# MOTOR_DRIVER.net
KiCad netlist of a schematic drawn in EAGLE
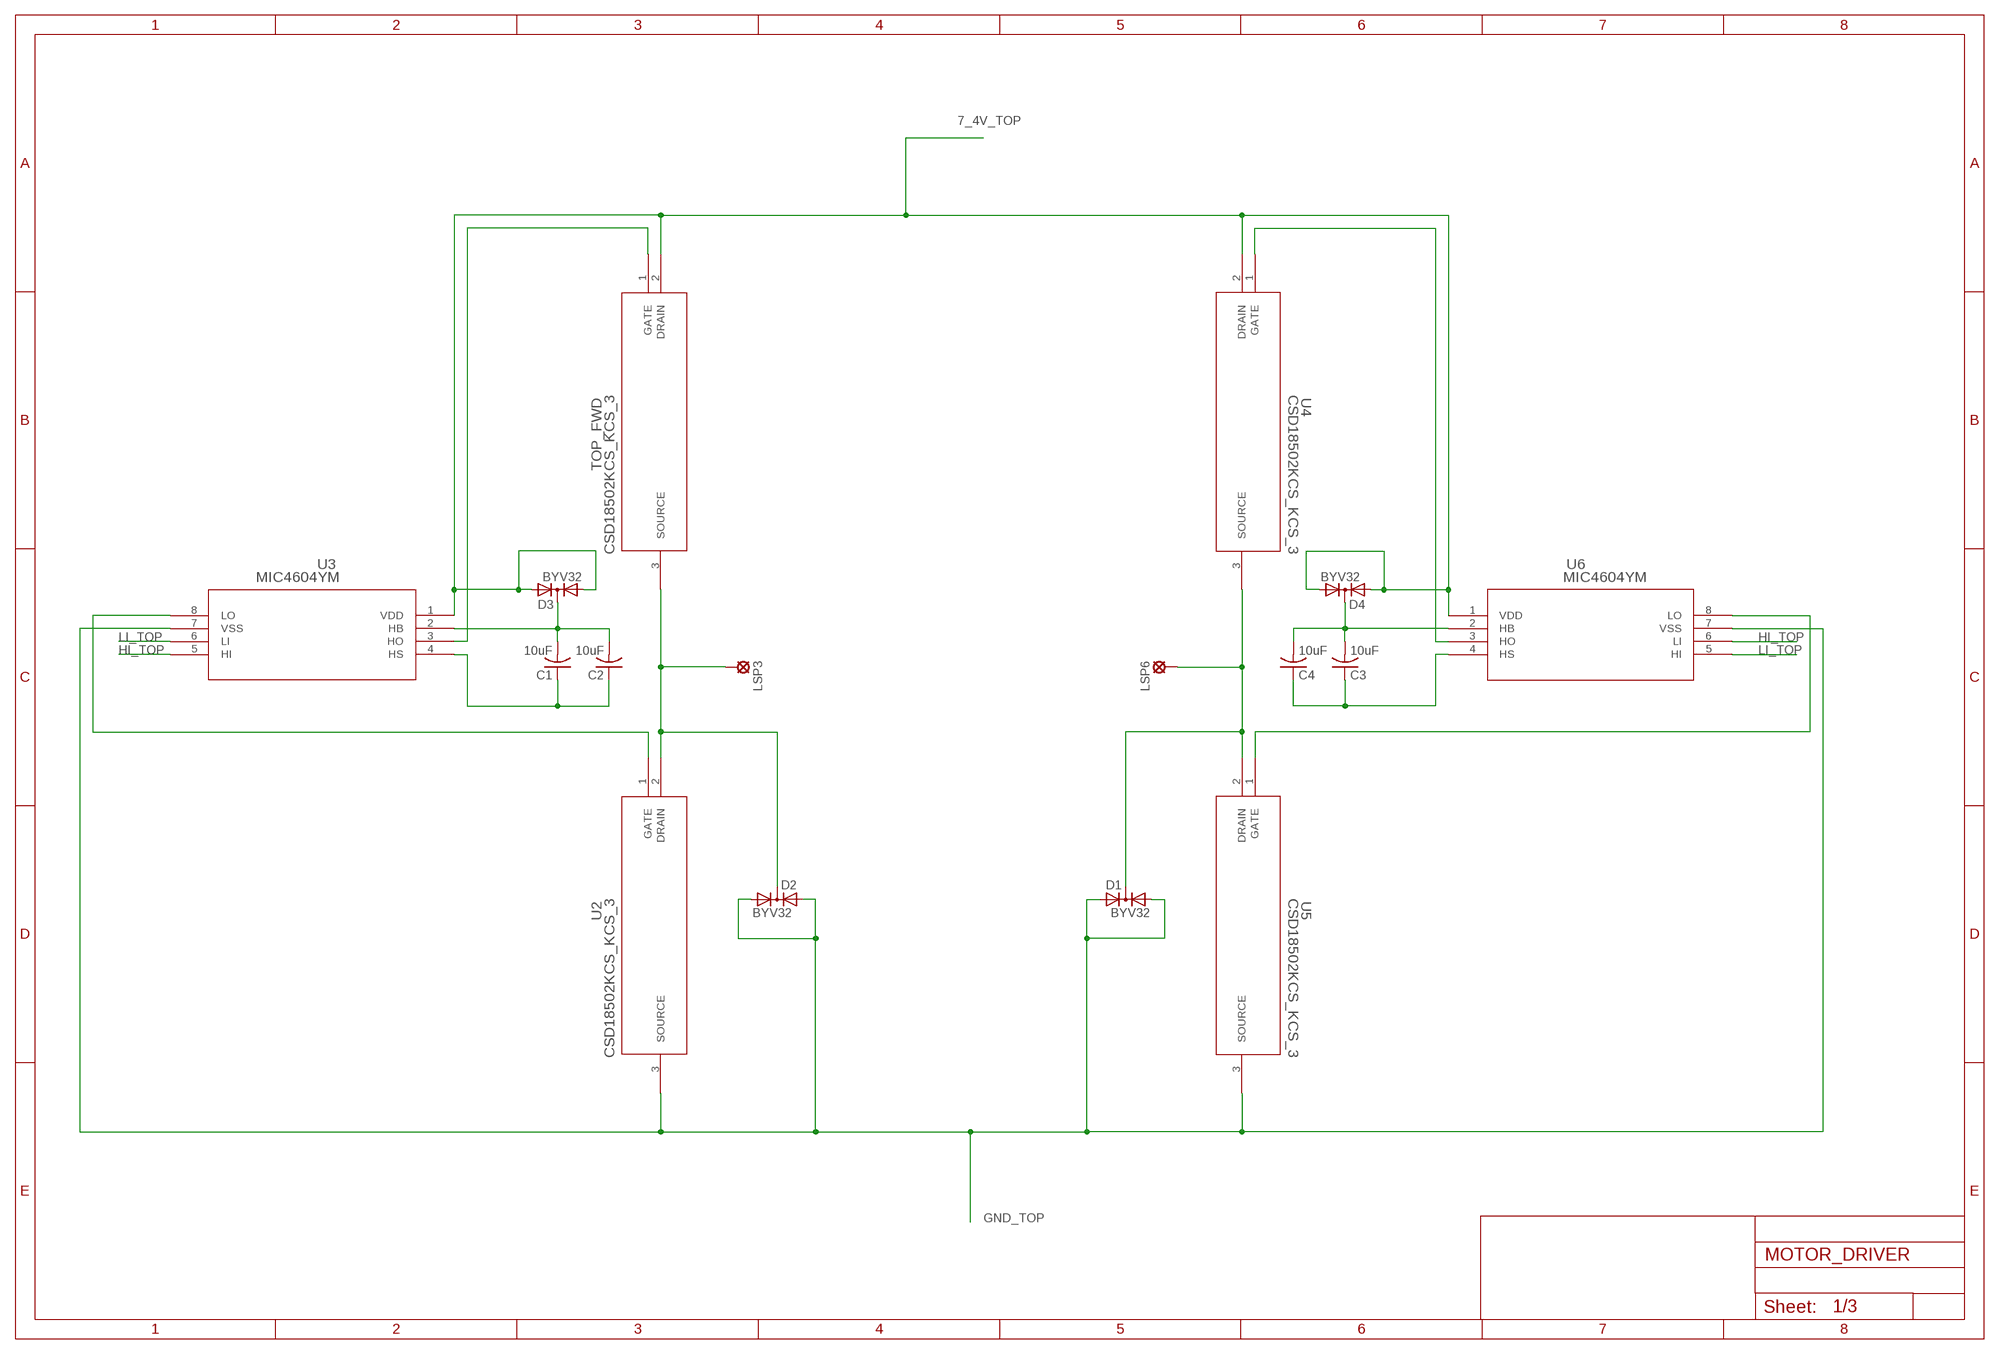
[diagram p0: schematic, sheet 1]
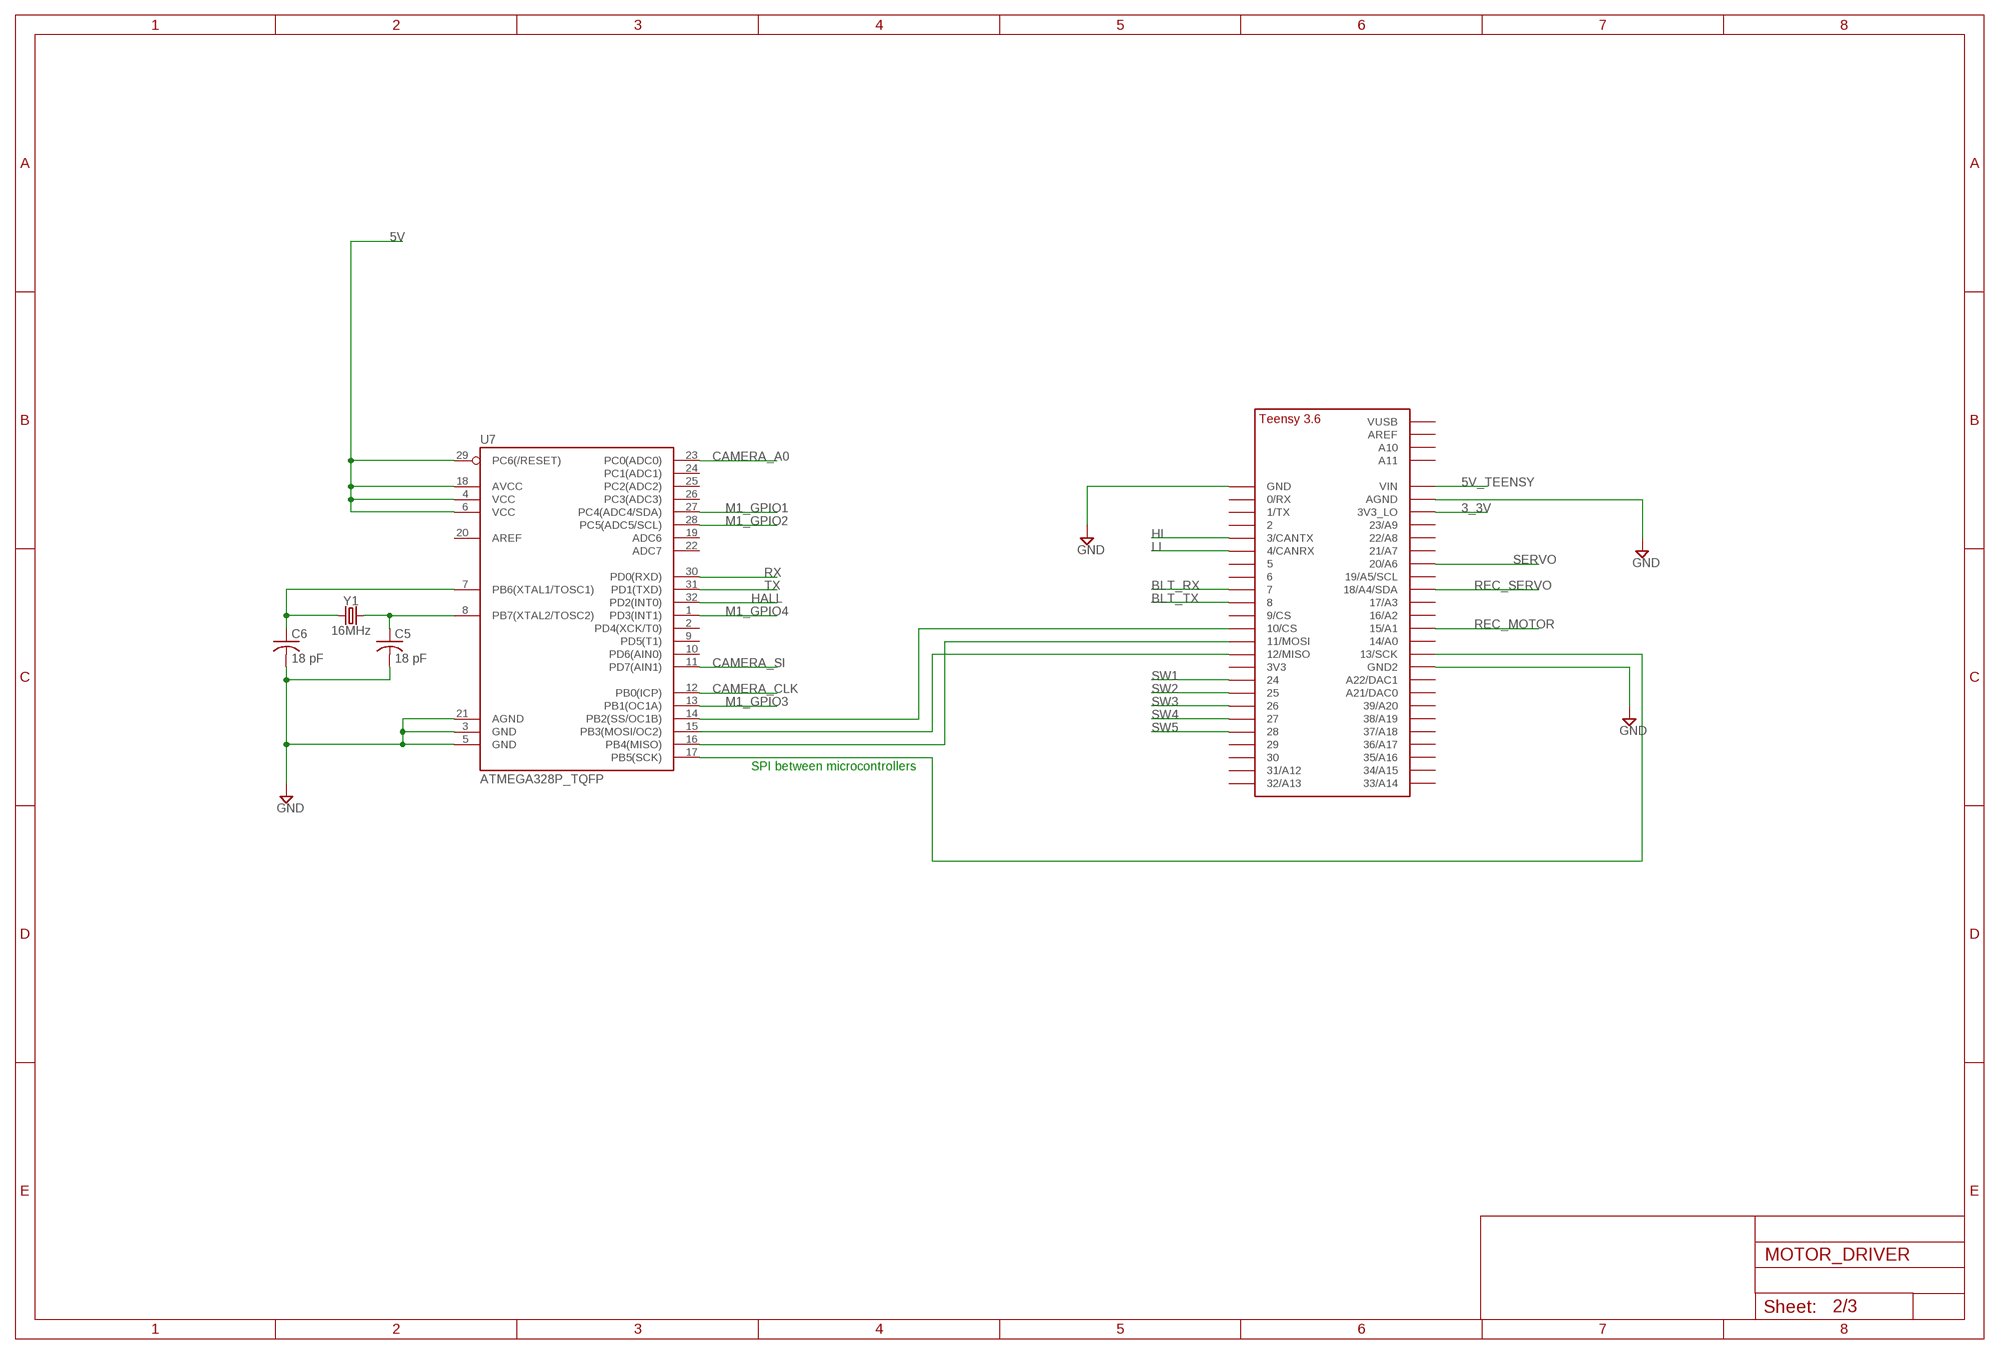
[diagram p1: schematic, sheet 2]
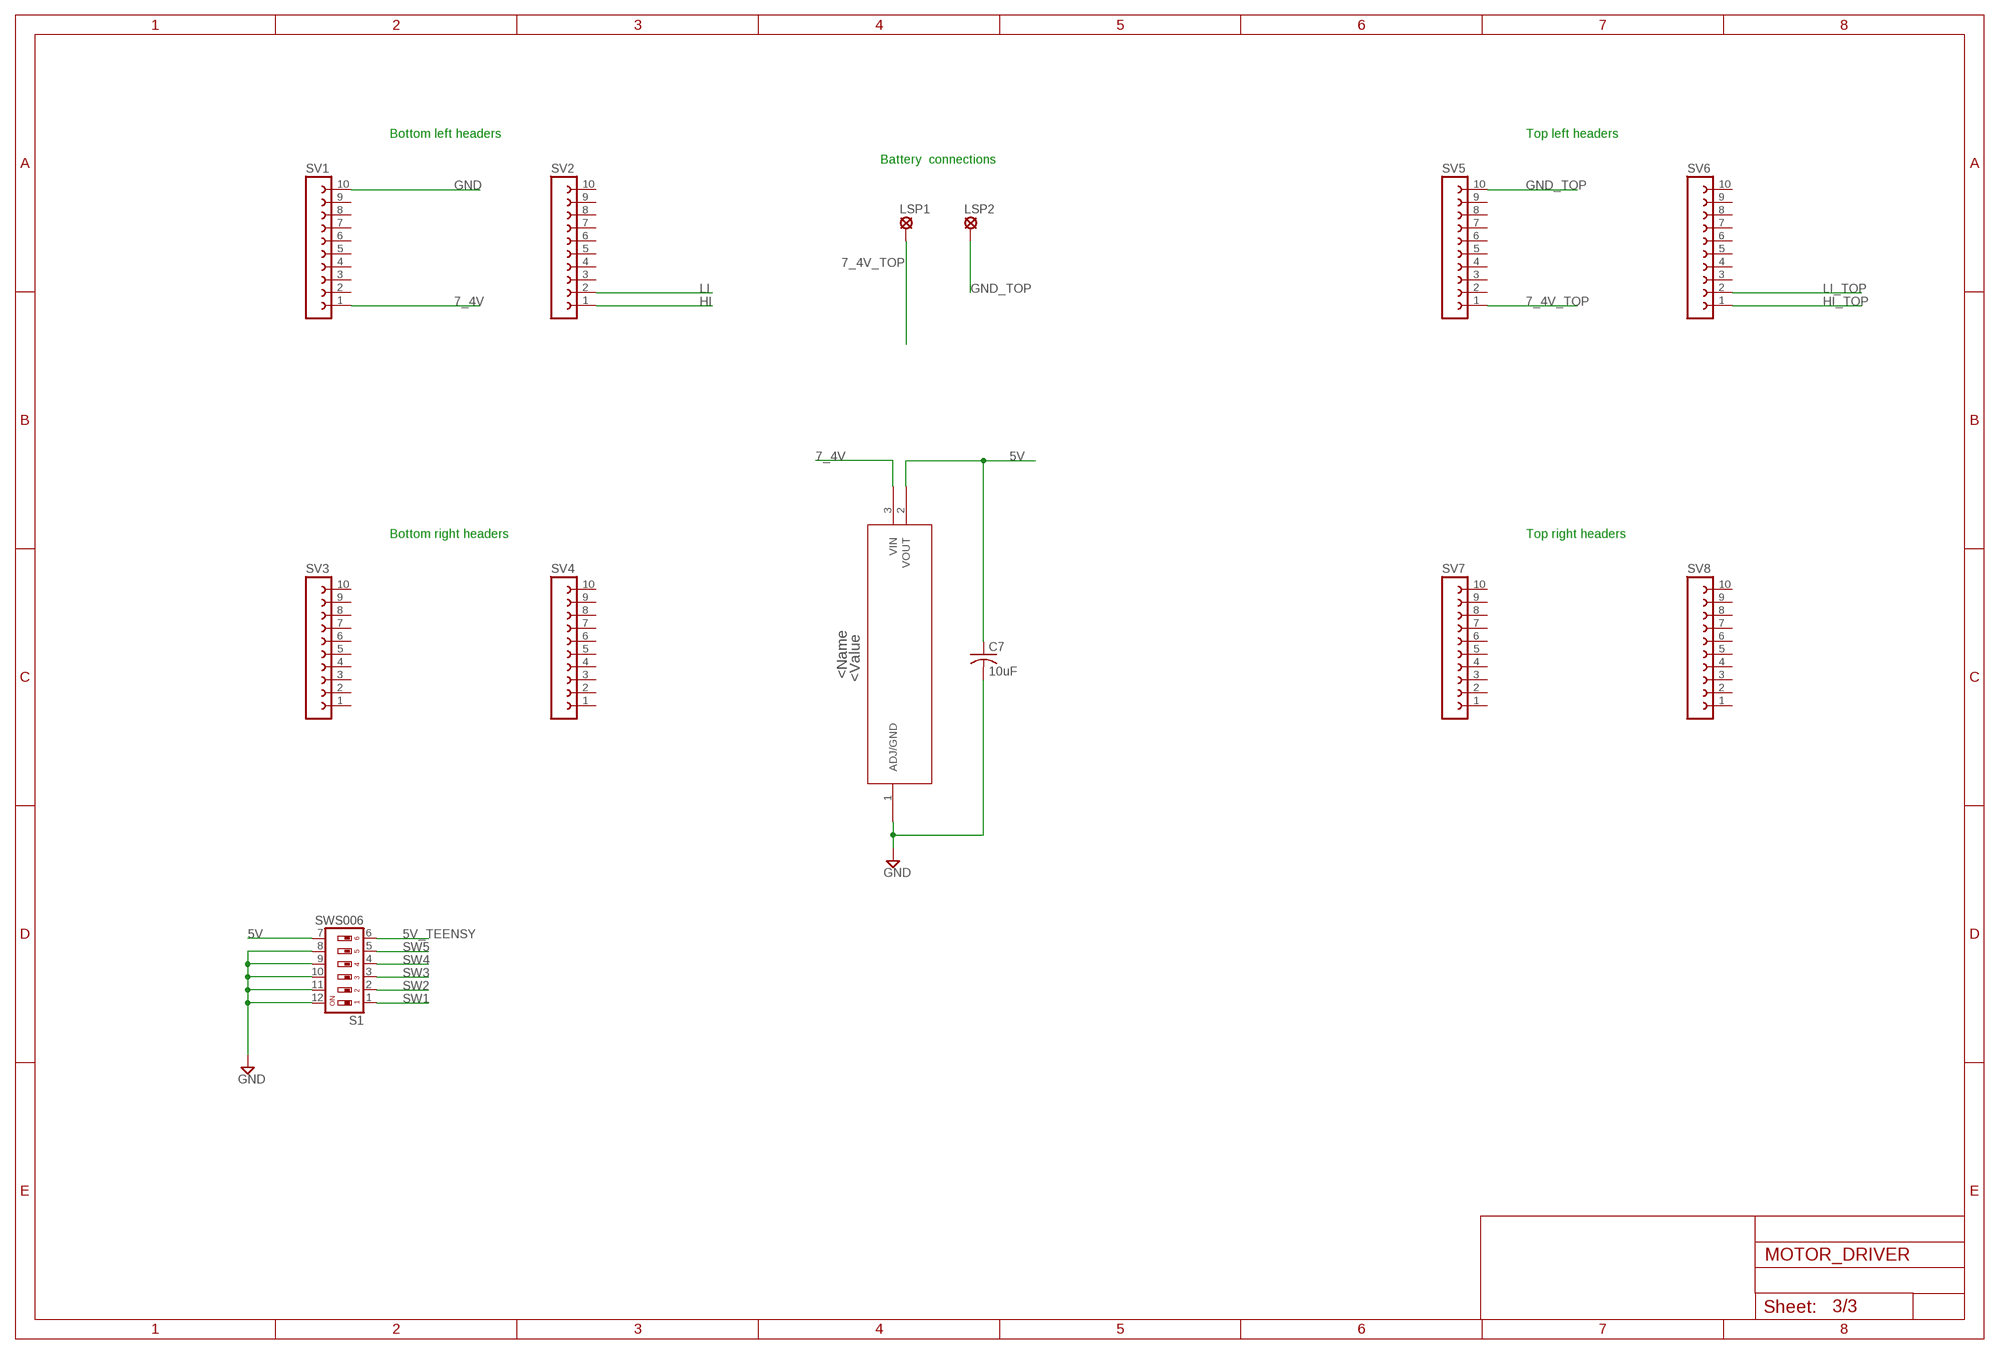
[diagram p2: schematic, sheet 3]

(export (version "E")
  (design (tool "Eeschema 10.0.6"))
  (components
    (comp (ref "C7")
      (value "10uF")
      (footprint "eagle-import:C050-025X075")
      (libsource (lib "eagle-import") (part "C-US050-025X075"))
    )
    (comp (ref "LSP1")
      (value "SE14")
      (footprint "eagle-import:SE14")
      (libsource (lib "eagle-import") (part "SE14"))
    )
    (comp (ref "LSP2")
      (value "SE14")
      (footprint "eagle-import:SE14")
      (libsource (lib "eagle-import") (part "SE14"))
    )
    (comp (ref "S1")
      (value "SWS006")
      (footprint "eagle-import:SMS-006")
      (libsource (lib "eagle-import") (part "SWS006"))
    )
    (comp (ref "SV1")
      (value "FE10-1")
      (footprint "eagle-import:FE10")
      (libsource (lib "eagle-import") (part "FE10-1"))
    )
    (comp (ref "SV2")
      (value "FE10-1")
      (footprint "eagle-import:FE10")
      (libsource (lib "eagle-import") (part "FE10-1"))
    )
    (comp (ref "SV3")
      (value "FE10-1")
      (footprint "eagle-import:FE10")
      (libsource (lib "eagle-import") (part "FE10-1"))
    )
    (comp (ref "SV4")
      (value "FE10-1")
      (footprint "eagle-import:FE10")
      (libsource (lib "eagle-import") (part "FE10-1"))
    )
    (comp (ref "SV5")
      (value "FE10-1")
      (footprint "eagle-import:FE10")
      (libsource (lib "eagle-import") (part "FE10-1"))
    )
    (comp (ref "SV6")
      (value "FE10-1")
      (footprint "eagle-import:FE10")
      (libsource (lib "eagle-import") (part "FE10-1"))
    )
    (comp (ref "SV7")
      (value "FE10-1")
      (footprint "eagle-import:FE10")
      (libsource (lib "eagle-import") (part "FE10-1"))
    )
    (comp (ref "SV8")
      (value "FE10-1")
      (footprint "eagle-import:FE10")
      (libsource (lib "eagle-import") (part "FE10-1"))
    )
    (comp (ref "U$2")
      (value "LM1086IT-5.0/NOPB")
      (footprint "eagle-import:T03B")
      (fields
        (field (name "MANUFACTURER_PART_NUMBER") "LM1086IT50")
        (field (name "COPYRIGHT") "Copyright C 2015 Accelerated Designs. All rights reserved")
      )
      (libsource (lib "eagle-import") (part "LM1086IT-5.0/NOPB"))
    )
    (comp (ref "C1")
      (value "10uF")
      (footprint "eagle-import:C025-050X050")
      (libsource (lib "eagle-import") (part "C-US025-050X050"))
    )
    (comp (ref "C2")
      (value "10uF")
      (footprint "eagle-import:C025-050X050")
      (libsource (lib "eagle-import") (part "C-US025-050X050"))
    )
    (comp (ref "C3")
      (value "10uF")
      (footprint "eagle-import:C025-050X050")
      (libsource (lib "eagle-import") (part "C-US025-050X050"))
    )
    (comp (ref "C4")
      (value "10uF")
      (footprint "eagle-import:C025-050X050")
      (libsource (lib "eagle-import") (part "C-US025-050X050"))
    )
    (comp (ref "D1")
      (value "BYV32")
      (footprint "eagle-import:TO220ABS")
      (libsource (lib "eagle-import") (part "BYV32"))
    )
    (comp (ref "D2")
      (value "BYV32")
      (footprint "eagle-import:TO220ABS")
      (libsource (lib "eagle-import") (part "BYV32"))
    )
    (comp (ref "D3")
      (value "BYV32")
      (footprint "eagle-import:TO220ABS")
      (libsource (lib "eagle-import") (part "BYV32"))
    )
    (comp (ref "D4")
      (value "BYV32")
      (footprint "eagle-import:TO220ABS")
      (libsource (lib "eagle-import") (part "BYV32"))
    )
    (comp (ref "LSP3")
      (value "SE14")
      (footprint "eagle-import:SE14")
      (libsource (lib "eagle-import") (part "SE14"))
    )
    (comp (ref "LSP6")
      (value "SE14")
      (footprint "eagle-import:SE14")
      (libsource (lib "eagle-import") (part "SE14"))
    )
    (comp (ref "TOP_FWD")
      (value "CSD18502KCS_KCS_3")
      (footprint "eagle-import:KCS3")
      (fields (field (name "MANUFACTURER_PART_NUMBER") "csd18502kcs_kcs_3"))
      (libsource (lib "eagle-import") (part "CSD18502KCS_KCS_3"))
    )
    (comp (ref "U2")
      (value "CSD18502KCS_KCS_3")
      (footprint "eagle-import:KCS3")
      (fields (field (name "MANUFACTURER_PART_NUMBER") "csd18502kcs_kcs_3"))
      (libsource (lib "eagle-import") (part "CSD18502KCS_KCS_3"))
    )
    (comp (ref "U3")
      (value "MIC4604YM")
      (footprint "eagle-import:SOIC-8_M")
      (fields (field (name "MANUFACTURER_PART_NUMBER") "mic4604ym"))
      (libsource (lib "eagle-import") (part "MIC4604YM"))
    )
    (comp (ref "U4")
      (value "CSD18502KCS_KCS_3")
      (footprint "eagle-import:KCS3")
      (fields (field (name "MANUFACTURER_PART_NUMBER") "csd18502kcs_kcs_3"))
      (libsource (lib "eagle-import") (part "CSD18502KCS_KCS_3"))
    )
    (comp (ref "U5")
      (value "CSD18502KCS_KCS_3")
      (footprint "eagle-import:KCS3")
      (fields (field (name "MANUFACTURER_PART_NUMBER") "csd18502kcs_kcs_3"))
      (libsource (lib "eagle-import") (part "CSD18502KCS_KCS_3"))
    )
    (comp (ref "U6")
      (value "MIC4604YM")
      (footprint "eagle-import:SOIC-8_M")
      (fields (field (name "MANUFACTURER_PART_NUMBER") "mic4604ym"))
      (libsource (lib "eagle-import") (part "MIC4604YM"))
    )
    (comp (ref "C5")
      (value "18 pF")
      (footprint "eagle-import:C025-024X044")
      (libsource (lib "eagle-import") (part "C-US025-024X044"))
    )
    (comp (ref "C6")
      (value "18 pF")
      (footprint "eagle-import:C025-024X044")
      (libsource (lib "eagle-import") (part "C-US025-024X044"))
    )
    (comp (ref "U$1")
      (value "TEENSY_3.5/3.6_BASIC")
      (footprint "eagle-import:TEENSY_3.5_3.6_BASIC")
      (libsource (lib "eagle-import") (part "TEENSY_3.5/3.6_BASIC"))
    )
    (comp (ref "U7")
      (value "ATMEGA328P_TQFP")
      (footprint "eagle-import:TQFP32-08")
      (libsource (lib "eagle-import") (part "ATMEGA328P_TQFP"))
    )
    (comp (ref "Y1")
      (value "16MHz")
      (footprint "eagle-import:HC49US")
      (libsource (lib "eagle-import") (part "CRYSTAL-16MHZPTH-HC49US"))
    )
  )
  (nets
    (net (code "1") (name "3_3V") (class "Default")
      (node (ref "U$1") (pin "3V3_LO") (pinfunction "3V3_LO_3V3_LO") (pintype "bidirectional"))
    )
    (net (code "2") (name "5V") (class "Default")
      (node (ref "C7") (pin "1") (pinfunction "1_1") (pintype "passive"))
      (node (ref "S1") (pin "7") (pinfunction "7_7") (pintype "passive"))
      (node (ref "U$2") (pin "2") (pinfunction "VOUT_2") (pintype "output"))
      (node (ref "U7") (pin "18") (pinfunction "AVCC_18") (pintype "bidirectional"))
      (node (ref "U7") (pin "29") (pinfunction "PC6(/RESET)_29") (pintype "bidirectional"))
      (node (ref "U7") (pin "4") (pinfunction "VCC_4") (pintype "bidirectional"))
      (node (ref "U7") (pin "6") (pinfunction "VCC_6") (pintype "bidirectional"))
    )
    (net (code "3") (name "5V_TEENSY") (class "Default")
      (node (ref "S1") (pin "6") (pinfunction "6_6") (pintype "passive"))
      (node (ref "U$1") (pin "VIN") (pinfunction "VIN_VIN") (pintype "bidirectional"))
    )
    (net (code "4") (name "7_4V") (class "Default")
      (node (ref "SV1") (pin "1") (pinfunction "1_1") (pintype "passive"))
      (node (ref "U$2") (pin "3") (pinfunction "VIN_3") (pintype "input"))
    )
    (net (code "5") (name "7_4V_TOP") (class "Default")
      (node (ref "D3") (pin "A1") (pinfunction "A1_A1") (pintype "passive"))
      (node (ref "D3") (pin "A2") (pinfunction "A2_A2") (pintype "passive"))
      (node (ref "D4") (pin "A1") (pinfunction "A1_A1") (pintype "passive"))
      (node (ref "D4") (pin "A2") (pinfunction "A2_A2") (pintype "passive"))
      (node (ref "LSP1") (pin "MP") (pinfunction "MP_MP") (pintype "passive"))
      (node (ref "SV5") (pin "1") (pinfunction "1_1") (pintype "passive"))
      (node (ref "TOP_FWD") (pin "2") (pinfunction "DRAIN_2") (pintype "passive"))
      (node (ref "U3") (pin "1") (pinfunction "VDD_1") (pintype "power_in"))
      (node (ref "U4") (pin "2") (pinfunction "DRAIN_2") (pintype "passive"))
      (node (ref "U6") (pin "1") (pinfunction "VDD_1") (pintype "power_in"))
    )
    (net (code "6") (name "BLT_RX") (class "Default")
      (node (ref "U$1") (pin "7") (pinfunction "7_7") (pintype "bidirectional"))
    )
    (net (code "7") (name "BLT_TX") (class "Default")
      (node (ref "U$1") (pin "8") (pinfunction "8_8") (pintype "bidirectional"))
    )
    (net (code "8") (name "CAMERA_A0") (class "Default")
      (node (ref "U7") (pin "23") (pinfunction "PC0(ADC0)_23") (pintype "bidirectional"))
    )
    (net (code "9") (name "CAMERA_CLK") (class "Default")
      (node (ref "U7") (pin "12") (pinfunction "PB0(ICP)_12") (pintype "bidirectional"))
    )
    (net (code "10") (name "CAMERA_SI") (class "Default")
      (node (ref "U7") (pin "11") (pinfunction "PD7(AIN1)_11") (pintype "bidirectional"))
    )
    (net (code "11") (name "GND") (class "Default")
      (node (ref "C5") (pin "2") (pinfunction "2_2") (pintype "passive"))
      (node (ref "C6") (pin "2") (pinfunction "2_2") (pintype "passive"))
      (node (ref "C7") (pin "2") (pinfunction "2_2") (pintype "passive"))
      (node (ref "S1") (pin "10") (pinfunction "10_10") (pintype "passive"))
      (node (ref "S1") (pin "11") (pinfunction "11_11") (pintype "passive"))
      (node (ref "S1") (pin "12") (pinfunction "12_12") (pintype "passive"))
      (node (ref "S1") (pin "8") (pinfunction "8_8") (pintype "passive"))
      (node (ref "S1") (pin "9") (pinfunction "9_9") (pintype "passive"))
      (node (ref "SV1") (pin "10") (pinfunction "10_10") (pintype "passive"))
      (node (ref "U$1") (pin "AGND") (pinfunction "AGND_AGND") (pintype "bidirectional"))
      (node (ref "U$1") (pin "GND") (pinfunction "GND_GND") (pintype "bidirectional"))
      (node (ref "U$1") (pin "GND2") (pinfunction "GND2_GND2") (pintype "bidirectional"))
      (node (ref "U$2") (pin "1") (pinfunction "ADJ/GND_1") (pintype "passive"))
      (node (ref "U7") (pin "21") (pinfunction "AGND_21") (pintype "bidirectional"))
      (node (ref "U7") (pin "3") (pinfunction "GND_3") (pintype "bidirectional"))
      (node (ref "U7") (pin "5") (pinfunction "GND_5") (pintype "bidirectional"))
    )
    (net (code "12") (name "GND_TOP") (class "Default")
      (node (ref "D1") (pin "A1") (pinfunction "A1_A1") (pintype "passive"))
      (node (ref "D1") (pin "A2") (pinfunction "A2_A2") (pintype "passive"))
      (node (ref "D2") (pin "A1") (pinfunction "A1_A1") (pintype "passive"))
      (node (ref "D2") (pin "A2") (pinfunction "A2_A2") (pintype "passive"))
      (node (ref "LSP2") (pin "MP") (pinfunction "MP_MP") (pintype "passive"))
      (node (ref "SV5") (pin "10") (pinfunction "10_10") (pintype "passive"))
      (node (ref "U2") (pin "3") (pinfunction "SOURCE_3") (pintype "passive"))
      (node (ref "U3") (pin "7") (pinfunction "VSS_7") (pintype "power_in"))
      (node (ref "U5") (pin "3") (pinfunction "SOURCE_3") (pintype "passive"))
      (node (ref "U6") (pin "7") (pinfunction "VSS_7") (pintype "power_in"))
    )
    (net (code "13") (name "HALL") (class "Default")
      (node (ref "U7") (pin "32") (pinfunction "PD2(INT0)_32") (pintype "bidirectional"))
    )
    (net (code "14") (name "HI") (class "Default")
      (node (ref "SV2") (pin "1") (pinfunction "1_1") (pintype "passive"))
      (node (ref "U$1") (pin "3/CANTX") (pinfunction "3/CANTX_3/CANTX") (pintype "bidirectional"))
    )
    (net (code "15") (name "HI_TOP") (class "Default")
      (node (ref "SV6") (pin "1") (pinfunction "1_1") (pintype "passive"))
      (node (ref "U3") (pin "5") (pinfunction "HI_5") (pintype "input"))
      (node (ref "U6") (pin "6") (pinfunction "LI_6") (pintype "input"))
    )
    (net (code "16") (name "LI") (class "Default")
      (node (ref "SV2") (pin "2") (pinfunction "2_2") (pintype "passive"))
      (node (ref "U$1") (pin "4/CANRX") (pinfunction "4/CANRX_4/CANRX") (pintype "bidirectional"))
    )
    (net (code "17") (name "LI_TOP") (class "Default")
      (node (ref "SV6") (pin "2") (pinfunction "2_2") (pintype "passive"))
      (node (ref "U3") (pin "6") (pinfunction "LI_6") (pintype "input"))
      (node (ref "U6") (pin "5") (pinfunction "HI_5") (pintype "input"))
    )
    (net (code "18") (name "M1_GPIO1") (class "Default")
      (node (ref "U7") (pin "27") (pinfunction "PC4(ADC4/SDA)_27") (pintype "bidirectional"))
    )
    (net (code "19") (name "M1_GPIO2") (class "Default")
      (node (ref "U7") (pin "28") (pinfunction "PC5(ADC5/SCL)_28") (pintype "bidirectional"))
    )
    (net (code "20") (name "M1_GPIO3") (class "Default")
      (node (ref "U7") (pin "13") (pinfunction "PB1(OC1A)_13") (pintype "bidirectional"))
    )
    (net (code "21") (name "M1_GPIO4") (class "Default")
      (node (ref "U7") (pin "1") (pinfunction "PD3(INT1)_1") (pintype "bidirectional"))
    )
    (net (code "22") (name "Net-(TOP_FWD-GATE)") (class "Default")
      (node (ref "TOP_FWD") (pin "1") (pinfunction "GATE_1") (pintype "passive"))
      (node (ref "U3") (pin "3") (pinfunction "HO_3") (pintype "output"))
    )
    (net (code "23") (name "Net-(TOP_FWD-SOURCE)") (class "Default")
      (node (ref "D2") (pin "C") (pinfunction "C_C") (pintype "passive"))
      (node (ref "LSP3") (pin "MP") (pinfunction "MP_MP") (pintype "passive"))
      (node (ref "TOP_FWD") (pin "3") (pinfunction "SOURCE_3") (pintype "passive"))
      (node (ref "U2") (pin "2") (pinfunction "DRAIN_2") (pintype "passive"))
    )
    (net (code "24") (name "Net-(U2-GATE)") (class "Default")
      (node (ref "U2") (pin "1") (pinfunction "GATE_1") (pintype "passive"))
      (node (ref "U3") (pin "8") (pinfunction "LO_8") (pintype "output"))
    )
    (net (code "25") (name "Net-(U3-HB)") (class "Default")
      (node (ref "C1") (pin "2") (pinfunction "2_2") (pintype "passive"))
      (node (ref "C2") (pin "2") (pinfunction "2_2") (pintype "passive"))
      (node (ref "D3") (pin "C") (pinfunction "C_C") (pintype "passive"))
      (node (ref "U3") (pin "2") (pinfunction "HB_2") (pintype "passive"))
    )
    (net (code "26") (name "Net-(U3-HS)") (class "Default")
      (node (ref "C1") (pin "1") (pinfunction "1_1") (pintype "passive"))
      (node (ref "C2") (pin "1") (pinfunction "1_1") (pintype "passive"))
      (node (ref "U3") (pin "4") (pinfunction "HS_4") (pintype "passive"))
    )
    (net (code "27") (name "Net-(U4-GATE)") (class "Default")
      (node (ref "U4") (pin "1") (pinfunction "GATE_1") (pintype "passive"))
      (node (ref "U6") (pin "3") (pinfunction "HO_3") (pintype "output"))
    )
    (net (code "28") (name "Net-(U4-SOURCE)") (class "Default")
      (node (ref "D1") (pin "C") (pinfunction "C_C") (pintype "passive"))
      (node (ref "LSP6") (pin "MP") (pinfunction "MP_MP") (pintype "passive"))
      (node (ref "U4") (pin "3") (pinfunction "SOURCE_3") (pintype "passive"))
      (node (ref "U5") (pin "2") (pinfunction "DRAIN_2") (pintype "passive"))
    )
    (net (code "29") (name "Net-(U5-GATE)") (class "Default")
      (node (ref "U5") (pin "1") (pinfunction "GATE_1") (pintype "passive"))
      (node (ref "U6") (pin "8") (pinfunction "LO_8") (pintype "output"))
    )
    (net (code "30") (name "Net-(U6-HB)") (class "Default")
      (node (ref "C3") (pin "2") (pinfunction "2_2") (pintype "passive"))
      (node (ref "C4") (pin "2") (pinfunction "2_2") (pintype "passive"))
      (node (ref "D4") (pin "C") (pinfunction "C_C") (pintype "passive"))
      (node (ref "U6") (pin "2") (pinfunction "HB_2") (pintype "passive"))
    )
    (net (code "31") (name "Net-(U6-HS)") (class "Default")
      (node (ref "C3") (pin "1") (pinfunction "1_1") (pintype "passive"))
      (node (ref "C4") (pin "1") (pinfunction "1_1") (pintype "passive"))
      (node (ref "U6") (pin "4") (pinfunction "HS_4") (pintype "passive"))
    )
    (net (code "32") (name "Net-(U7-PB2(SS{slash}OC1B))") (class "Default")
      (node (ref "U$1") (pin "10/CS") (pinfunction "10/CS_10/CS") (pintype "bidirectional"))
      (node (ref "U7") (pin "14") (pinfunction "PB2(SS/OC1B)_14") (pintype "bidirectional"))
    )
    (net (code "33") (name "Net-(U7-PB3(MOSI{slash}OC2))") (class "Default")
      (node (ref "U$1") (pin "12/MISO") (pinfunction "12/MISO_12/MISO") (pintype "bidirectional"))
      (node (ref "U7") (pin "15") (pinfunction "PB3(MOSI/OC2)_15") (pintype "bidirectional"))
    )
    (net (code "34") (name "Net-(U7-PB4(MISO))") (class "Default")
      (node (ref "U$1") (pin "11/MOSI") (pinfunction "11/MOSI_11/MOSI") (pintype "bidirectional"))
      (node (ref "U7") (pin "16") (pinfunction "PB4(MISO)_16") (pintype "bidirectional"))
    )
    (net (code "35") (name "Net-(U7-PB5(SCK))") (class "Default")
      (node (ref "U$1") (pin "13/SCK") (pinfunction "13/SCK_13/SCK") (pintype "bidirectional"))
      (node (ref "U7") (pin "17") (pinfunction "PB5(SCK)_17") (pintype "bidirectional"))
    )
    (net (code "36") (name "Net-(U7-PB6(XTAL1{slash}TOSC1))") (class "Default")
      (node (ref "C6") (pin "1") (pinfunction "1_1") (pintype "passive"))
      (node (ref "U7") (pin "7") (pinfunction "PB6(XTAL1/TOSC1)_7") (pintype "bidirectional"))
      (node (ref "Y1") (pin "1") (pinfunction "1_1") (pintype "passive"))
    )
    (net (code "37") (name "Net-(U7-PB7(XTAL2{slash}TOSC2))") (class "Default")
      (node (ref "C5") (pin "1") (pinfunction "1_1") (pintype "passive"))
      (node (ref "U7") (pin "8") (pinfunction "PB7(XTAL2/TOSC2)_8") (pintype "bidirectional"))
      (node (ref "Y1") (pin "2") (pinfunction "2_2") (pintype "passive"))
    )
    (net (code "38") (name "REC_MOTOR") (class "Default")
      (node (ref "U$1") (pin "15/A1") (pinfunction "15/A1_15/A1") (pintype "bidirectional"))
    )
    (net (code "39") (name "REC_SERVO") (class "Default")
      (node (ref "U$1") (pin "18/A4/SDA") (pinfunction "18/A4/SDA_18/A4/SDA") (pintype "bidirectional"))
    )
    (net (code "40") (name "RX") (class "Default")
      (node (ref "U7") (pin "30") (pinfunction "PD0(RXD)_30") (pintype "bidirectional"))
    )
    (net (code "41") (name "SERVO") (class "Default")
      (node (ref "U$1") (pin "20/A6") (pinfunction "20/A6_20/A6") (pintype "bidirectional"))
    )
    (net (code "42") (name "SW1") (class "Default")
      (node (ref "S1") (pin "1") (pinfunction "1_1") (pintype "passive"))
      (node (ref "U$1") (pin "24") (pinfunction "24_24") (pintype "bidirectional"))
    )
    (net (code "43") (name "SW2") (class "Default")
      (node (ref "S1") (pin "2") (pinfunction "2_2") (pintype "passive"))
      (node (ref "U$1") (pin "25") (pinfunction "25_25") (pintype "bidirectional"))
    )
    (net (code "44") (name "SW3") (class "Default")
      (node (ref "S1") (pin "3") (pinfunction "3_3") (pintype "passive"))
      (node (ref "U$1") (pin "26") (pinfunction "26_26") (pintype "bidirectional"))
    )
    (net (code "45") (name "SW4") (class "Default")
      (node (ref "S1") (pin "4") (pinfunction "4_4") (pintype "passive"))
      (node (ref "U$1") (pin "27") (pinfunction "27_27") (pintype "bidirectional"))
    )
    (net (code "46") (name "SW5") (class "Default")
      (node (ref "S1") (pin "5") (pinfunction "5_5") (pintype "passive"))
      (node (ref "U$1") (pin "28") (pinfunction "28_28") (pintype "bidirectional"))
    )
    (net (code "47") (name "TX") (class "Default")
      (node (ref "U7") (pin "31") (pinfunction "PD1(TXD)_31") (pintype "bidirectional"))
    )
    (net (code "48") (name "unconnected-(SV1-Pad2)") (class "Default")
      (node (ref "SV1") (pin "2") (pinfunction "2_2") (pintype "passive"))
    )
    (net (code "49") (name "unconnected-(SV1-Pad3)") (class "Default")
      (node (ref "SV1") (pin "3") (pinfunction "3_3") (pintype "passive"))
    )
    (net (code "50") (name "unconnected-(SV1-Pad4)") (class "Default")
      (node (ref "SV1") (pin "4") (pinfunction "4_4") (pintype "passive"))
    )
    (net (code "51") (name "unconnected-(SV1-Pad5)") (class "Default")
      (node (ref "SV1") (pin "5") (pinfunction "5_5") (pintype "passive"))
    )
    (net (code "52") (name "unconnected-(SV1-Pad6)") (class "Default")
      (node (ref "SV1") (pin "6") (pinfunction "6_6") (pintype "passive"))
    )
    (net (code "53") (name "unconnected-(SV1-Pad7)") (class "Default")
      (node (ref "SV1") (pin "7") (pinfunction "7_7") (pintype "passive"))
    )
    (net (code "54") (name "unconnected-(SV1-Pad8)") (class "Default")
      (node (ref "SV1") (pin "8") (pinfunction "8_8") (pintype "passive"))
    )
    (net (code "55") (name "unconnected-(SV1-Pad9)") (class "Default")
      (node (ref "SV1") (pin "9") (pinfunction "9_9") (pintype "passive"))
    )
    (net (code "56") (name "unconnected-(SV2-Pad3)") (class "Default")
      (node (ref "SV2") (pin "3") (pinfunction "3_3") (pintype "passive"))
    )
    (net (code "57") (name "unconnected-(SV2-Pad4)") (class "Default")
      (node (ref "SV2") (pin "4") (pinfunction "4_4") (pintype "passive"))
    )
    (net (code "58") (name "unconnected-(SV2-Pad5)") (class "Default")
      (node (ref "SV2") (pin "5") (pinfunction "5_5") (pintype "passive"))
    )
    (net (code "59") (name "unconnected-(SV2-Pad6)") (class "Default")
      (node (ref "SV2") (pin "6") (pinfunction "6_6") (pintype "passive"))
    )
    (net (code "60") (name "unconnected-(SV2-Pad7)") (class "Default")
      (node (ref "SV2") (pin "7") (pinfunction "7_7") (pintype "passive"))
    )
    (net (code "61") (name "unconnected-(SV2-Pad8)") (class "Default")
      (node (ref "SV2") (pin "8") (pinfunction "8_8") (pintype "passive"))
    )
    (net (code "62") (name "unconnected-(SV2-Pad9)") (class "Default")
      (node (ref "SV2") (pin "9") (pinfunction "9_9") (pintype "passive"))
    )
    (net (code "63") (name "unconnected-(SV2-Pad10)") (class "Default")
      (node (ref "SV2") (pin "10") (pinfunction "10_10") (pintype "passive"))
    )
    (net (code "64") (name "unconnected-(SV3-Pad1)") (class "Default")
      (node (ref "SV3") (pin "1") (pinfunction "1_1") (pintype "passive"))
    )
    (net (code "65") (name "unconnected-(SV3-Pad2)") (class "Default")
      (node (ref "SV3") (pin "2") (pinfunction "2_2") (pintype "passive"))
    )
    (net (code "66") (name "unconnected-(SV3-Pad3)") (class "Default")
      (node (ref "SV3") (pin "3") (pinfunction "3_3") (pintype "passive"))
    )
    (net (code "67") (name "unconnected-(SV3-Pad4)") (class "Default")
      (node (ref "SV3") (pin "4") (pinfunction "4_4") (pintype "passive"))
    )
    (net (code "68") (name "unconnected-(SV3-Pad5)") (class "Default")
      (node (ref "SV3") (pin "5") (pinfunction "5_5") (pintype "passive"))
    )
    (net (code "69") (name "unconnected-(SV3-Pad6)") (class "Default")
      (node (ref "SV3") (pin "6") (pinfunction "6_6") (pintype "passive"))
    )
    (net (code "70") (name "unconnected-(SV3-Pad7)") (class "Default")
      (node (ref "SV3") (pin "7") (pinfunction "7_7") (pintype "passive"))
    )
    (net (code "71") (name "unconnected-(SV3-Pad8)") (class "Default")
      (node (ref "SV3") (pin "8") (pinfunction "8_8") (pintype "passive"))
    )
    (net (code "72") (name "unconnected-(SV3-Pad9)") (class "Default")
      (node (ref "SV3") (pin "9") (pinfunction "9_9") (pintype "passive"))
    )
    (net (code "73") (name "unconnected-(SV3-Pad10)") (class "Default")
      (node (ref "SV3") (pin "10") (pinfunction "10_10") (pintype "passive"))
    )
    (net (code "74") (name "unconnected-(SV4-Pad1)") (class "Default")
      (node (ref "SV4") (pin "1") (pinfunction "1_1") (pintype "passive"))
    )
    (net (code "75") (name "unconnected-(SV4-Pad2)") (class "Default")
      (node (ref "SV4") (pin "2") (pinfunction "2_2") (pintype "passive"))
    )
    (net (code "76") (name "unconnected-(SV4-Pad3)") (class "Default")
      (node (ref "SV4") (pin "3") (pinfunction "3_3") (pintype "passive"))
    )
    (net (code "77") (name "unconnected-(SV4-Pad4)") (class "Default")
      (node (ref "SV4") (pin "4") (pinfunction "4_4") (pintype "passive"))
    )
    (net (code "78") (name "unconnected-(SV4-Pad5)") (class "Default")
      (node (ref "SV4") (pin "5") (pinfunction "5_5") (pintype "passive"))
    )
    (net (code "79") (name "unconnected-(SV4-Pad6)") (class "Default")
      (node (ref "SV4") (pin "6") (pinfunction "6_6") (pintype "passive"))
    )
    (net (code "80") (name "unconnected-(SV4-Pad7)") (class "Default")
      (node (ref "SV4") (pin "7") (pinfunction "7_7") (pintype "passive"))
    )
    (net (code "81") (name "unconnected-(SV4-Pad8)") (class "Default")
      (node (ref "SV4") (pin "8") (pinfunction "8_8") (pintype "passive"))
    )
    (net (code "82") (name "unconnected-(SV4-Pad9)") (class "Default")
      (node (ref "SV4") (pin "9") (pinfunction "9_9") (pintype "passive"))
    )
    (net (code "83") (name "unconnected-(SV4-Pad10)") (class "Default")
      (node (ref "SV4") (pin "10") (pinfunction "10_10") (pintype "passive"))
    )
    (net (code "84") (name "unconnected-(SV5-Pad2)") (class "Default")
      (node (ref "SV5") (pin "2") (pinfunction "2_2") (pintype "passive"))
    )
    (net (code "85") (name "unconnected-(SV5-Pad3)") (class "Default")
      (node (ref "SV5") (pin "3") (pinfunction "3_3") (pintype "passive"))
    )
    (net (code "86") (name "unconnected-(SV5-Pad4)") (class "Default")
      (node (ref "SV5") (pin "4") (pinfunction "4_4") (pintype "passive"))
    )
    (net (code "87") (name "unconnected-(SV5-Pad5)") (class "Default")
      (node (ref "SV5") (pin "5") (pinfunction "5_5") (pintype "passive"))
    )
    (net (code "88") (name "unconnected-(SV5-Pad6)") (class "Default")
      (node (ref "SV5") (pin "6") (pinfunction "6_6") (pintype "passive"))
    )
    (net (code "89") (name "unconnected-(SV5-Pad7)") (class "Default")
      (node (ref "SV5") (pin "7") (pinfunction "7_7") (pintype "passive"))
    )
    (net (code "90") (name "unconnected-(SV5-Pad8)") (class "Default")
      (node (ref "SV5") (pin "8") (pinfunction "8_8") (pintype "passive"))
    )
    (net (code "91") (name "unconnected-(SV5-Pad9)") (class "Default")
      (node (ref "SV5") (pin "9") (pinfunction "9_9") (pintype "passive"))
    )
    (net (code "92") (name "unconnected-(SV6-Pad3)") (class "Default")
      (node (ref "SV6") (pin "3") (pinfunction "3_3") (pintype "passive"))
    )
    (net (code "93") (name "unconnected-(SV6-Pad4)") (class "Default")
      (node (ref "SV6") (pin "4") (pinfunction "4_4") (pintype "passive"))
    )
    (net (code "94") (name "unconnected-(SV6-Pad5)") (class "Default")
      (node (ref "SV6") (pin "5") (pinfunction "5_5") (pintype "passive"))
    )
    (net (code "95") (name "unconnected-(SV6-Pad6)") (class "Default")
      (node (ref "SV6") (pin "6") (pinfunction "6_6") (pintype "passive"))
    )
    (net (code "96") (name "unconnected-(SV6-Pad7)") (class "Default")
      (node (ref "SV6") (pin "7") (pinfunction "7_7") (pintype "passive"))
    )
    (net (code "97") (name "unconnected-(SV6-Pad8)") (class "Default")
      (node (ref "SV6") (pin "8") (pinfunction "8_8") (pintype "passive"))
    )
    (net (code "98") (name "unconnected-(SV6-Pad9)") (class "Default")
      (node (ref "SV6") (pin "9") (pinfunction "9_9") (pintype "passive"))
    )
    (net (code "99") (name "unconnected-(SV6-Pad10)") (class "Default")
      (node (ref "SV6") (pin "10") (pinfunction "10_10") (pintype "passive"))
    )
    (net (code "100") (name "unconnected-(SV7-Pad1)") (class "Default")
      (node (ref "SV7") (pin "1") (pinfunction "1_1") (pintype "passive"))
    )
    (net (code "101") (name "unconnected-(SV7-Pad2)") (class "Default")
      (node (ref "SV7") (pin "2") (pinfunction "2_2") (pintype "passive"))
    )
    (net (code "102") (name "unconnected-(SV7-Pad3)") (class "Default")
      (node (ref "SV7") (pin "3") (pinfunction "3_3") (pintype "passive"))
    )
    (net (code "103") (name "unconnected-(SV7-Pad4)") (class "Default")
      (node (ref "SV7") (pin "4") (pinfunction "4_4") (pintype "passive"))
    )
    (net (code "104") (name "unconnected-(SV7-Pad5)") (class "Default")
      (node (ref "SV7") (pin "5") (pinfunction "5_5") (pintype "passive"))
    )
    (net (code "105") (name "unconnected-(SV7-Pad6)") (class "Default")
      (node (ref "SV7") (pin "6") (pinfunction "6_6") (pintype "passive"))
    )
    (net (code "106") (name "unconnected-(SV7-Pad7)") (class "Default")
      (node (ref "SV7") (pin "7") (pinfunction "7_7") (pintype "passive"))
    )
    (net (code "107") (name "unconnected-(SV7-Pad8)") (class "Default")
      (node (ref "SV7") (pin "8") (pinfunction "8_8") (pintype "passive"))
    )
    (net (code "108") (name "unconnected-(SV7-Pad9)") (class "Default")
      (node (ref "SV7") (pin "9") (pinfunction "9_9") (pintype "passive"))
    )
    (net (code "109") (name "unconnected-(SV7-Pad10)") (class "Default")
      (node (ref "SV7") (pin "10") (pinfunction "10_10") (pintype "passive"))
    )
    (net (code "110") (name "unconnected-(SV8-Pad1)") (class "Default")
      (node (ref "SV8") (pin "1") (pinfunction "1_1") (pintype "passive"))
    )
    (net (code "111") (name "unconnected-(SV8-Pad2)") (class "Default")
      (node (ref "SV8") (pin "2") (pinfunction "2_2") (pintype "passive"))
    )
    (net (code "112") (name "unconnected-(SV8-Pad3)") (class "Default")
      (node (ref "SV8") (pin "3") (pinfunction "3_3") (pintype "passive"))
    )
    (net (code "113") (name "unconnected-(SV8-Pad4)") (class "Default")
      (node (ref "SV8") (pin "4") (pinfunction "4_4") (pintype "passive"))
    )
    (net (code "114") (name "unconnected-(SV8-Pad5)") (class "Default")
      (node (ref "SV8") (pin "5") (pinfunction "5_5") (pintype "passive"))
    )
    (net (code "115") (name "unconnected-(SV8-Pad6)") (class "Default")
      (node (ref "SV8") (pin "6") (pinfunction "6_6") (pintype "passive"))
    )
    (net (code "116") (name "unconnected-(SV8-Pad7)") (class "Default")
      (node (ref "SV8") (pin "7") (pinfunction "7_7") (pintype "passive"))
    )
    (net (code "117") (name "unconnected-(SV8-Pad8)") (class "Default")
      (node (ref "SV8") (pin "8") (pinfunction "8_8") (pintype "passive"))
    )
    (net (code "118") (name "unconnected-(SV8-Pad9)") (class "Default")
      (node (ref "SV8") (pin "9") (pinfunction "9_9") (pintype "passive"))
    )
    (net (code "119") (name "unconnected-(SV8-Pad10)") (class "Default")
      (node (ref "SV8") (pin "10") (pinfunction "10_10") (pintype "passive"))
    )
    (net (code "120") (name "unconnected-(U$1-A21{slash}DAC0-Pad21{slash}DAC0)") (class "Default")
      (node (ref "U$1") (pin "21/DAC0") (pinfunction "A21/DAC0_21/DAC0") (pintype "bidirectional"))
    )
    (net (code "121") (name "unconnected-(U$1-Pad0{slash}RX)") (class "Default")
      (node (ref "U$1") (pin "0/RX") (pinfunction "0/RX_0/RX") (pintype "bidirectional"))
    )
    (net (code "122") (name "unconnected-(U$1-Pad1{slash}TX)") (class "Default")
      (node (ref "U$1") (pin "1/TX") (pinfunction "1/TX_1/TX") (pintype "bidirectional"))
    )
    (net (code "123") (name "unconnected-(U$1-Pad2)") (class "Default")
      (node (ref "U$1") (pin "2") (pinfunction "2_2") (pintype "bidirectional"))
    )
    (net (code "124") (name "unconnected-(U$1-Pad3V3)") (class "Default")
      (node (ref "U$1") (pin "3V3") (pinfunction "3V3_3V3") (pintype "bidirectional"))
    )
    (net (code "125") (name "unconnected-(U$1-Pad5)") (class "Default")
      (node (ref "U$1") (pin "5") (pinfunction "5_5") (pintype "bidirectional"))
    )
    (net (code "126") (name "unconnected-(U$1-Pad6)") (class "Default")
      (node (ref "U$1") (pin "6") (pinfunction "6_6") (pintype "bidirectional"))
    )
    (net (code "127") (name "unconnected-(U$1-Pad9{slash}CS)") (class "Default")
      (node (ref "U$1") (pin "9/CS") (pinfunction "9/CS_9/CS") (pintype "bidirectional"))
    )
    (net (code "128") (name "unconnected-(U$1-Pad14{slash}A0)") (class "Default")
      (node (ref "U$1") (pin "14/A0") (pinfunction "14/A0_14/A0") (pintype "bidirectional"))
    )
    (net (code "129") (name "unconnected-(U$1-Pad16{slash}A2)") (class "Default")
      (node (ref "U$1") (pin "16/A2") (pinfunction "16/A2_16/A2") (pintype "bidirectional"))
    )
    (net (code "130") (name "unconnected-(U$1-Pad17{slash}A3)") (class "Default")
      (node (ref "U$1") (pin "17/A3") (pinfunction "17/A3_17/A3") (pintype "bidirectional"))
    )
    (net (code "131") (name "unconnected-(U$1-Pad19{slash}A5{slash}SCL)") (class "Default")
      (node (ref "U$1") (pin "19/A5/SCL") (pinfunction "19/A5/SCL_19/A5/SCL") (pintype "bidirectional"))
    )
    (net (code "132") (name "unconnected-(U$1-Pad21{slash}A7)") (class "Default")
      (node (ref "U$1") (pin "21/A7") (pinfunction "21/A7_21/A7") (pintype "bidirectional"))
    )
    (net (code "133") (name "unconnected-(U$1-Pad22{slash}A8)") (class "Default")
      (node (ref "U$1") (pin "22/A8") (pinfunction "22/A8_22/A8") (pintype "bidirectional"))
    )
    (net (code "134") (name "unconnected-(U$1-Pad23{slash}A9)") (class "Default")
      (node (ref "U$1") (pin "23/A9") (pinfunction "23/A9_23/A9") (pintype "bidirectional"))
    )
    (net (code "135") (name "unconnected-(U$1-Pad29)") (class "Default")
      (node (ref "U$1") (pin "29") (pinfunction "29_29") (pintype "bidirectional"))
    )
    (net (code "136") (name "unconnected-(U$1-Pad30)") (class "Default")
      (node (ref "U$1") (pin "30") (pinfunction "30_30") (pintype "bidirectional"))
    )
    (net (code "137") (name "unconnected-(U$1-Pad31{slash}A12)") (class "Default")
      (node (ref "U$1") (pin "31/A12") (pinfunction "31/A12_31/A12") (pintype "bidirectional"))
    )
    (net (code "138") (name "unconnected-(U$1-Pad32{slash}A13)") (class "Default")
      (node (ref "U$1") (pin "32/A13") (pinfunction "32/A13_32/A13") (pintype "bidirectional"))
    )
    (net (code "139") (name "unconnected-(U$1-Pad33{slash}A14)") (class "Default")
      (node (ref "U$1") (pin "33/A14") (pinfunction "33/A14_33/A14") (pintype "bidirectional"))
    )
    (net (code "140") (name "unconnected-(U$1-Pad34{slash}A15)") (class "Default")
      (node (ref "U$1") (pin "34/A15") (pinfunction "34/A15_34/A15") (pintype "bidirectional"))
    )
    (net (code "141") (name "unconnected-(U$1-Pad35{slash}A16)") (class "Default")
      (node (ref "U$1") (pin "35/A16") (pinfunction "35/A16_35/A16") (pintype "bidirectional"))
    )
    (net (code "142") (name "unconnected-(U$1-Pad36{slash}A17)") (class "Default")
      (node (ref "U$1") (pin "36/A17") (pinfunction "36/A17_36/A17") (pintype "bidirectional"))
    )
    (net (code "143") (name "unconnected-(U$1-Pad37{slash}A18)") (class "Default")
      (node (ref "U$1") (pin "37/A18") (pinfunction "37/A18_37/A18") (pintype "bidirectional"))
    )
    (net (code "144") (name "unconnected-(U$1-Pad38{slash}A19)") (class "Default")
      (node (ref "U$1") (pin "38/A19") (pinfunction "38/A19_38/A19") (pintype "bidirectional"))
    )
    (net (code "145") (name "unconnected-(U$1-Pad39{slash}A20)") (class "Default")
      (node (ref "U$1") (pin "39/A20") (pinfunction "39/A20_39/A20") (pintype "bidirectional"))
    )
    (net (code "146") (name "unconnected-(U$1-PadA10)") (class "Default")
      (node (ref "U$1") (pin "A10") (pinfunction "A10_A10") (pintype "bidirectional"))
    )
    (net (code "147") (name "unconnected-(U$1-PadA11)") (class "Default")
      (node (ref "U$1") (pin "A11") (pinfunction "A11_A11") (pintype "bidirectional"))
    )
    (net (code "148") (name "unconnected-(U$1-PadA22{slash}DAC1)") (class "Default")
      (node (ref "U$1") (pin "A22/DAC1") (pinfunction "A22/DAC1_A22/DAC1") (pintype "bidirectional"))
    )
    (net (code "149") (name "unconnected-(U$1-PadAREF)") (class "Default")
      (node (ref "U$1") (pin "AREF") (pinfunction "AREF_AREF") (pintype "bidirectional"))
    )
    (net (code "150") (name "unconnected-(U$1-PadVUSB)") (class "Default")
      (node (ref "U$1") (pin "VUSB") (pinfunction "VUSB_VUSB") (pintype "bidirectional"))
    )
    (net (code "151") (name "unconnected-(U7-ADC6-Pad19)") (class "Default")
      (node (ref "U7") (pin "19") (pinfunction "ADC6_19") (pintype "bidirectional"))
    )
    (net (code "152") (name "unconnected-(U7-ADC7-Pad22)") (class "Default")
      (node (ref "U7") (pin "22") (pinfunction "ADC7_22") (pintype "bidirectional"))
    )
    (net (code "153") (name "unconnected-(U7-AREF-Pad20)") (class "Default")
      (node (ref "U7") (pin "20") (pinfunction "AREF_20") (pintype "bidirectional"))
    )
    (net (code "154") (name "unconnected-(U7-PC1(ADC1)-Pad24)") (class "Default")
      (node (ref "U7") (pin "24") (pinfunction "PC1(ADC1)_24") (pintype "bidirectional"))
    )
    (net (code "155") (name "unconnected-(U7-PC2(ADC2)-Pad25)") (class "Default")
      (node (ref "U7") (pin "25") (pinfunction "PC2(ADC2)_25") (pintype "bidirectional"))
    )
    (net (code "156") (name "unconnected-(U7-PC3(ADC3)-Pad26)") (class "Default")
      (node (ref "U7") (pin "26") (pinfunction "PC3(ADC3)_26") (pintype "bidirectional"))
    )
    (net (code "157") (name "unconnected-(U7-PD4(XCK{slash}T0)-Pad2)") (class "Default")
      (node (ref "U7") (pin "2") (pinfunction "PD4(XCK/T0)_2") (pintype "bidirectional"))
    )
    (net (code "158") (name "unconnected-(U7-PD5(T1)-Pad9)") (class "Default")
      (node (ref "U7") (pin "9") (pinfunction "PD5(T1)_9") (pintype "bidirectional"))
    )
    (net (code "159") (name "unconnected-(U7-PD6(AIN0)-Pad10)") (class "Default")
      (node (ref "U7") (pin "10") (pinfunction "PD6(AIN0)_10") (pintype "bidirectional"))
    )
  )
)
